# 03_-_Power.net
KiCad netlist of a schematic drawn in Altium Designer
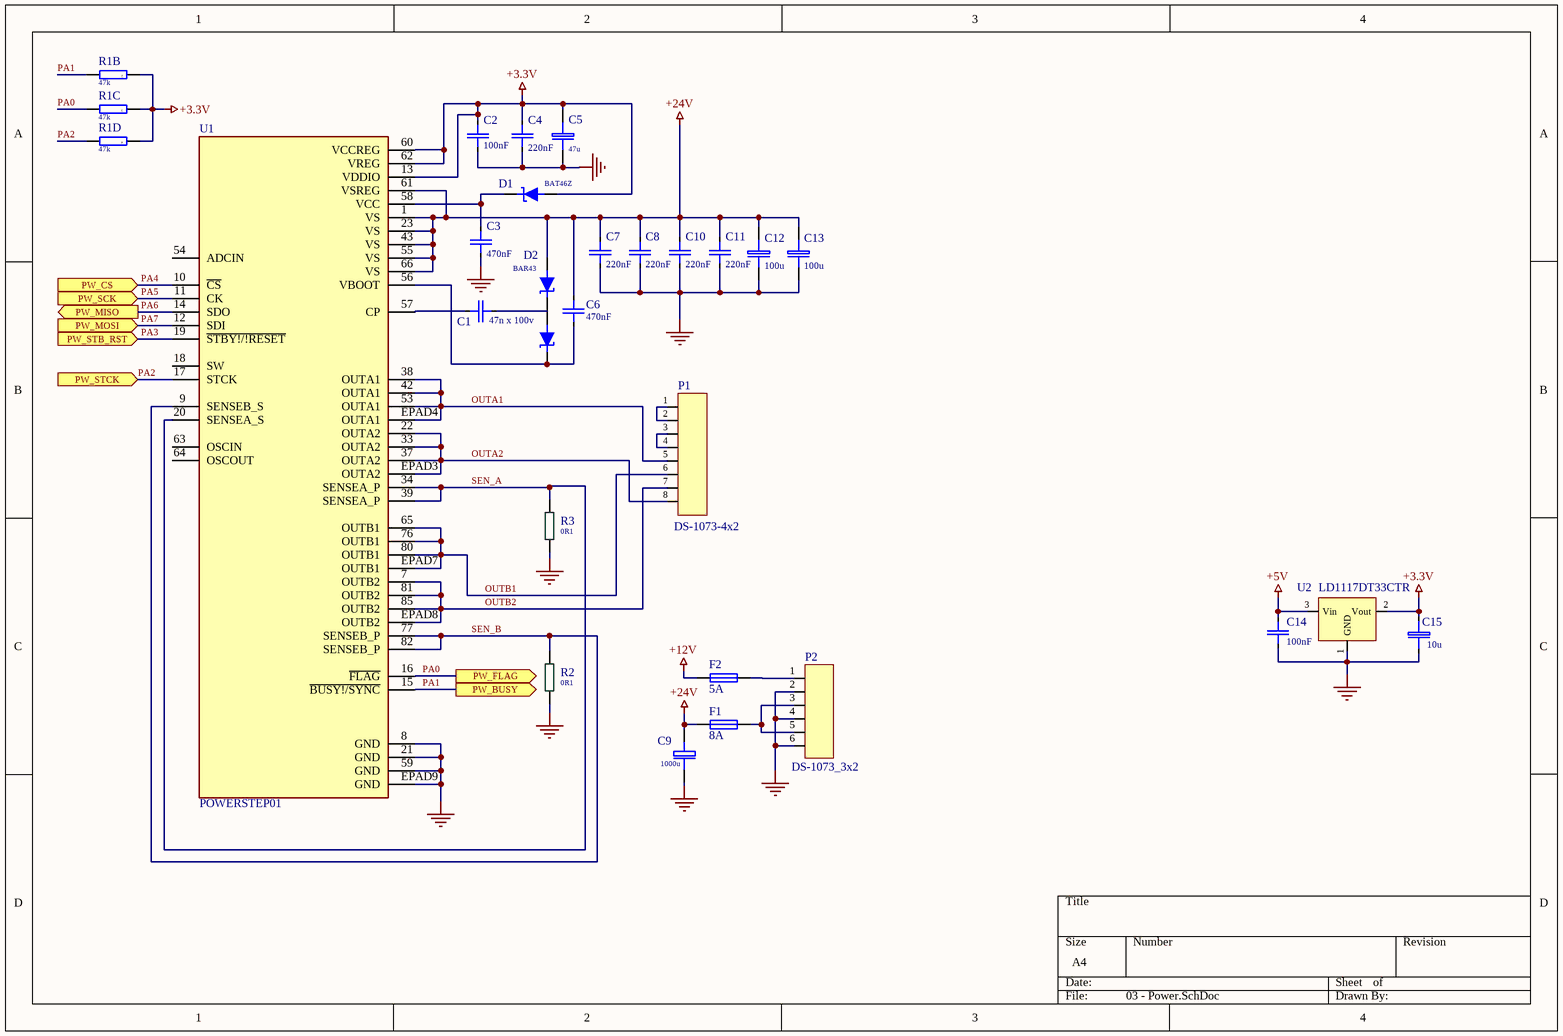
[diagram p0: 03 - Power.SchDoc]

(export (version "E")
  (design (tool "Eeschema 10.0.6"))
  (components
    (comp (ref "C1")
      (value "47n x 100v")
      (footprint "CAP: 0805")
      (description "SMD-0805")
      (libsource (lib "RCL_SMD_Integrated_Library") (part "C-0805"))
    )
    (comp (ref "C2")
      (value "100nF")
      (footprint "CAP: 0805")
      (description "SMD-0805")
      (libsource (lib "RCL_SMD_Integrated_Library") (part "C-0805"))
    )
    (comp (ref "C3")
      (value "470nF")
      (footprint "CAP: 0805")
      (description "SMD-0805")
      (libsource (lib "RCL_SMD_Integrated_Library") (part "C-0805"))
    )
    (comp (ref "C4")
      (value "220nF")
      (footprint "CAP: 0805")
      (description "SMD-0805")
      (libsource (lib "RCL_SMD_Integrated_Library") (part "C-0805"))
    )
    (comp (ref "C5")
      (value "47u")
      (footprint "EL SMD Case C D5x5.3 h5.4(0505)")
      (description "EL 50V SMD Case C D5x5.3 h5.4")
      (libsource (lib "SMD-RCL") (part "EL 10u/50V"))
    )
    (comp (ref "C6")
      (value "470nF")
      (footprint "CAP: 0805")
      (description "SMD-0805")
      (libsource (lib "RCL_SMD_Integrated_Library") (part "C-0805"))
    )
    (comp (ref "C7")
      (value "220nF")
      (footprint "CAP: 0805")
      (description "SMD-0805")
      (libsource (lib "RCL_SMD_Integrated_Library") (part "C-0805"))
    )
    (comp (ref "C8")
      (value "220nF")
      (footprint "CAP: 0805")
      (description "SMD-0805")
      (libsource (lib "RCL_SMD_Integrated_Library") (part "C-0805"))
    )
    (comp (ref "C9")
      (value "1000u")
      (footprint "El-d13-h21-F5.08")
      (description "35V 105C 34m 1.8A 5000h")
      (libsource (lib "Cap-El") (part "1000u-35V 105F"))
    )
    (comp (ref "C10")
      (value "220nF")
      (footprint "CAP: 0805")
      (description "SMD-0805")
      (libsource (lib "RCL_SMD_Integrated_Library") (part "C-0805"))
    )
    (comp (ref "C11")
      (value "220nF")
      (footprint "CAP: 0805")
      (description "SMD-0805")
      (libsource (lib "RCL_SMD_Integrated_Library") (part "C-0805"))
    )
    (comp (ref "C12")
      (value "100u")
      (footprint "EL SMD Case G D10x10.3 h10.2(1010)")
      (description "EL 35V SMD Case G D10x10.3h10.5")
      (libsource (lib "SMD-RCL") (part "EL 100u/35V"))
    )
    (comp (ref "C13")
      (value "100u")
      (footprint "EL SMD Case G D10x10.3 h10.2(1010)")
      (description "EL 35V SMD Case G D10x10.3h10.5")
      (libsource (lib "SMD-RCL") (part "EL 100u/35V"))
    )
    (comp (ref "C14")
      (value "100nF")
      (footprint "CAP: 0805")
      (description "SMD-0805")
      (libsource (lib "RCL_SMD_Integrated_Library") (part "C-0805"))
    )
    (comp (ref "C15")
      (value "10u")
      (footprint "EL Case A (3216-18)")
      (description "El Case A (2012-12)")
      (libsource (lib "RCL_SMD_Integrated_Library") (part "EL 10u/16V Tant."))
    )
    (comp (ref "D1")
      (value "BAT46Z")
      (footprint "SOD123")
      (description "SMD-SOT123 60V 15mA 2.2pF 1nS")
      (libsource (lib "Diodes") (part "1N6263"))
    )
    (comp (ref "D2")
      (value "BAR43")
      (footprint "SOT23")
      (description "SMD-SOT23 30V 0.2A 5nS 10pF")
      (libsource (lib "Diodes") (part "BAT54S"))
    )
    (comp (ref "F1")
      (value "8A")
      (footprint "Littelfuse 0451/453")
      (description "0451003")
      (libsource (lib "stm32_Integrated_Library") (part "Littelfuse 0451"))
    )
    (comp (ref "F2")
      (value "5A")
      (footprint "Littelfuse 0451/453")
      (description "0451003")
      (libsource (lib "stm32_Integrated_Library") (part "Littelfuse 0451"))
    )
    (comp (ref "P1")
      (value "DS-1073-4x2")
      (footprint "DS-1073-4x2")
      (libsource (lib "stm32_Integrated_Library") (part "DS-1073-4x2"))
    )
    (comp (ref "P2")
      (value "DS-1073_3x2")
      (footprint "DS-1073-2x3")
      (libsource (lib "stm32_Integrated_Library") (part "DS-1073_3x2"))
    )
    (comp (ref "R1")
      (value "47k")
      (footprint "RM4x0603")
      (description "SMD 4RM-0603 1\\16W 5%")
      (libsource (lib "SMD-RCL") (part "4RM-0603"))
    )
    (comp (ref "R2")
      (value "0R1")
      (footprint "R2512")
      (description "SMD 2512 1W 5% 200V")
      (libsource (lib "SMD-RCL") (part "R-2512"))
    )
    (comp (ref "R3")
      (value "0R1")
      (footprint "R2512")
      (description "SMD 2512 1W 5% 200V")
      (libsource (lib "SMD-RCL") (part "R-2512"))
    )
    (comp (ref "U1")
      (value "POWERSTEP01")
      (footprint "POWERSTEP01")
      (description "Bipolar Motor Driver Power MOSFET SPI 89-VFQFPN _11x14_")
      (fields (field (name "MF") "STMicroelectronics"))
      (libsource (lib "stm32_Integrated_Library") (part "POWERSTEP01"))
    )
    (comp (ref "U2")
      (value "LD1117DT33CTR")
      (footprint "DPAK")
      (libsource (lib "stm32_Integrated_Library") (part "LD1117DT33CTR"))
    )
  )
  (nets
    (net (code "1") (name "+3.3V") (class "Default")
      (node (ref "C15") (pin "1") (pinfunction "1_1") (pintype "passive"))
      (node (ref "C2") (pin "2") (pinfunction "2_2") (pintype "passive"))
      (node (ref "C4") (pin "1") (pinfunction "1_1") (pintype "passive"))
      (node (ref "C5") (pin "1") (pinfunction "+_1") (pintype "passive"))
      (node (ref "D1") (pin "1") (pinfunction "A_1") (pintype "passive"))
      (node (ref "R1") (pin "2") (pinfunction "2_2") (pintype "passive"))
      (node (ref "R1") (pin "3") (pinfunction "3_3") (pintype "passive"))
      (node (ref "R1") (pin "4") (pinfunction "4_4") (pintype "passive"))
      (node (ref "U1") (pin "13") (pinfunction "VDDIO_13") (pintype "power_in"))
      (node (ref "U1") (pin "60") (pinfunction "VCCREG_60") (pintype "power_in"))
      (node (ref "U1") (pin "62") (pinfunction "VREG_62") (pintype "power_in"))
      (node (ref "U2") (pin "2") (pinfunction "Vout_2") (pintype "passive"))
    )
    (net (code "2") (name "+5V") (class "Default")
      (node (ref "C14") (pin "2") (pinfunction "2_2") (pintype "passive"))
      (node (ref "U2") (pin "3") (pinfunction "Vin_3") (pintype "passive"))
    )
    (net (code "3") (name "+12V") (class "Default")
      (node (ref "F2") (pin "1") (pinfunction "1_1") (pintype "passive"))
    )
    (net (code "4") (name "+24V") (class "Default")
      (node (ref "C10") (pin "1") (pinfunction "1_1") (pintype "passive"))
      (node (ref "C11") (pin "1") (pinfunction "1_1") (pintype "passive"))
      (node (ref "C12") (pin "1") (pinfunction "1_1") (pintype "passive"))
      (node (ref "C13") (pin "1") (pinfunction "1_1") (pintype "passive"))
      (node (ref "C6") (pin "1") (pinfunction "1_1") (pintype "passive"))
      (node (ref "C7") (pin "1") (pinfunction "1_1") (pintype "passive"))
      (node (ref "C8") (pin "1") (pinfunction "1_1") (pintype "passive"))
      (node (ref "C9") (pin "1") (pinfunction "1_1") (pintype "passive"))
      (node (ref "D2") (pin "1") (pinfunction "1_1") (pintype "passive"))
      (node (ref "F1") (pin "1") (pinfunction "1_1") (pintype "passive"))
      (node (ref "U1") (pin "1") (pinfunction "VS_1") (pintype "passive"))
      (node (ref "U1") (pin "23") (pinfunction "VS_23") (pintype "passive"))
      (node (ref "U1") (pin "43") (pinfunction "VS_43") (pintype "passive"))
      (node (ref "U1") (pin "55") (pinfunction "VS_55") (pintype "passive"))
      (node (ref "U1") (pin "61") (pinfunction "VSREG_61") (pintype "passive"))
      (node (ref "U1") (pin "66") (pinfunction "VS_66") (pintype "passive"))
    )
    (net (code "5") (name "/OUTA1") (class "Default")
      (node (ref "P1") (pin "5") (pintype "passive"))
      (node (ref "U1") (pin "38") (pinfunction "OUTA1_38") (pintype "power_in"))
      (node (ref "U1") (pin "42") (pinfunction "OUTA1_42") (pintype "power_in"))
      (node (ref "U1") (pin "53") (pinfunction "OUTA1_53") (pintype "power_in"))
      (node (ref "U1") (pin "EPAD4") (pinfunction "OUTA1_EPAD4") (pintype "power_in"))
    )
    (net (code "6") (name "/OUTA2") (class "Default")
      (node (ref "P1") (pin "8") (pintype "passive"))
      (node (ref "U1") (pin "22") (pinfunction "OUTA2_22") (pintype "power_in"))
      (node (ref "U1") (pin "33") (pinfunction "OUTA2_33") (pintype "power_in"))
      (node (ref "U1") (pin "37") (pinfunction "OUTA2_37") (pintype "power_in"))
      (node (ref "U1") (pin "EPAD3") (pinfunction "OUTA2_EPAD3") (pintype "power_in"))
    )
    (net (code "7") (name "/OUTB1") (class "Default")
      (node (ref "P1") (pin "6") (pintype "passive"))
      (node (ref "U1") (pin "65") (pinfunction "OUTB1_65") (pintype "power_in"))
      (node (ref "U1") (pin "76") (pinfunction "OUTB1_76") (pintype "power_in"))
      (node (ref "U1") (pin "80") (pinfunction "OUTB1_80") (pintype "power_in"))
      (node (ref "U1") (pin "EPAD7") (pinfunction "OUTB1_EPAD7") (pintype "power_in"))
    )
    (net (code "8") (name "/OUTB2") (class "Default")
      (node (ref "P1") (pin "7") (pintype "passive"))
      (node (ref "U1") (pin "7") (pinfunction "OUTB2_7") (pintype "power_in"))
      (node (ref "U1") (pin "81") (pinfunction "OUTB2_81") (pintype "power_in"))
      (node (ref "U1") (pin "85") (pinfunction "OUTB2_85") (pintype "power_in"))
      (node (ref "U1") (pin "EPAD8") (pinfunction "OUTB2_EPAD8") (pintype "power_in"))
    )
    (net (code "9") (name "/PA0") (class "Default")
      (node (ref "R1") (pin "6") (pinfunction "6_6") (pintype "passive"))
      (node (ref "U1") (pin "16") (pinfunction "~{FLAG}_16") (pintype "passive"))
    )
    (net (code "10") (name "/PA1") (class "Default")
      (node (ref "R1") (pin "7") (pinfunction "7_7") (pintype "passive"))
      (node (ref "U1") (pin "15") (pinfunction "~{BUSY!/SYNC}_15") (pintype "passive"))
    )
    (net (code "11") (name "/PA2") (class "Default")
      (node (ref "R1") (pin "5") (pinfunction "5_5") (pintype "passive"))
      (node (ref "U1") (pin "17") (pinfunction "STCK_17") (pintype "passive"))
    )
    (net (code "12") (name "/PA3") (class "Default")
      (node (ref "U1") (pin "19") (pinfunction "~{STBY!/!RESET}_19") (pintype "passive"))
    )
    (net (code "13") (name "/PA4") (class "Default")
      (node (ref "U1") (pin "10") (pinfunction "~{CS}_10") (pintype "passive"))
    )
    (net (code "14") (name "/PA5") (class "Default")
      (node (ref "U1") (pin "11") (pinfunction "CK_11") (pintype "passive"))
    )
    (net (code "15") (name "/PA6") (class "Default")
      (node (ref "U1") (pin "14") (pinfunction "SDO_14") (pintype "passive"))
    )
    (net (code "16") (name "/PA7") (class "Default")
      (node (ref "U1") (pin "12") (pinfunction "SDI_12") (pintype "passive"))
    )
    (net (code "17") (name "/SEN_A") (class "Default")
      (node (ref "R3") (pin "2") (pinfunction "2_2") (pintype "passive"))
      (node (ref "U1") (pin "20") (pinfunction "SENSEA_S_20") (pintype "passive"))
      (node (ref "U1") (pin "34") (pinfunction "SENSEA_P_34") (pintype "passive"))
      (node (ref "U1") (pin "39") (pinfunction "SENSEA_P_39") (pintype "passive"))
    )
    (net (code "18") (name "/SEN_B") (class "Default")
      (node (ref "R2") (pin "2") (pinfunction "2_2") (pintype "passive"))
      (node (ref "U1") (pin "77") (pinfunction "SENSEB_P_77") (pintype "passive"))
      (node (ref "U1") (pin "82") (pinfunction "SENSEB_P_82") (pintype "passive"))
      (node (ref "U1") (pin "9") (pinfunction "SENSEB_S_9") (pintype "passive"))
    )
    (net (code "19") (name "GND") (class "Default")
      (node (ref "C10") (pin "2") (pinfunction "2_2") (pintype "passive"))
      (node (ref "C11") (pin "2") (pinfunction "2_2") (pintype "passive"))
      (node (ref "C12") (pin "2") (pinfunction "2_2") (pintype "passive"))
      (node (ref "C13") (pin "2") (pinfunction "2_2") (pintype "passive"))
      (node (ref "C14") (pin "1") (pinfunction "1_1") (pintype "passive"))
      (node (ref "C15") (pin "2") (pinfunction "2_2") (pintype "passive"))
      (node (ref "C2") (pin "1") (pinfunction "1_1") (pintype "passive"))
      (node (ref "C3") (pin "2") (pinfunction "2_2") (pintype "passive"))
      (node (ref "C4") (pin "2") (pinfunction "2_2") (pintype "passive"))
      (node (ref "C5") (pin "2") (pinfunction "-_2") (pintype "passive"))
      (node (ref "C7") (pin "2") (pinfunction "2_2") (pintype "passive"))
      (node (ref "C8") (pin "2") (pinfunction "2_2") (pintype "passive"))
      (node (ref "C9") (pin "2") (pinfunction "2_2") (pintype "passive"))
      (node (ref "P2") (pin "2") (pintype "passive"))
      (node (ref "P2") (pin "4") (pintype "passive"))
      (node (ref "P2") (pin "6") (pintype "passive"))
      (node (ref "R2") (pin "1") (pinfunction "1_1") (pintype "passive"))
      (node (ref "R3") (pin "1") (pinfunction "1_1") (pintype "passive"))
      (node (ref "U1") (pin "21") (pinfunction "GND_21") (pintype "power_in"))
      (node (ref "U1") (pin "59") (pinfunction "GND_59") (pintype "power_in"))
      (node (ref "U1") (pin "8") (pinfunction "GND_8") (pintype "power_in"))
      (node (ref "U1") (pin "EPAD9") (pinfunction "GND_EPAD9") (pintype "power_in"))
      (node (ref "U2") (pin "1") (pinfunction "GND_1") (pintype "passive"))
    )
    (net (code "20") (name "Net-(C1-Pad2)") (class "Default")
      (node (ref "C1") (pin "2") (pinfunction "2_2") (pintype "passive"))
      (node (ref "D2") (pin "3") (pinfunction "3_3") (pintype "passive"))
    )
    (net (code "21") (name "Net-(D1-C)") (class "Default")
      (node (ref "C3") (pin "1") (pinfunction "1_1") (pintype "passive"))
      (node (ref "D1") (pin "2") (pinfunction "C_2") (pintype "passive"))
      (node (ref "U1") (pin "58") (pinfunction "VCC_58") (pintype "power_in"))
    )
    (net (code "22") (name "Net-(F1-Pad2)") (class "Default")
      (node (ref "F1") (pin "2") (pinfunction "2_2") (pintype "passive"))
      (node (ref "P2") (pin "3") (pintype "passive"))
      (node (ref "P2") (pin "5") (pintype "passive"))
    )
    (net (code "23") (name "Net-(F2-Pad2)") (class "Default")
      (node (ref "F2") (pin "2") (pinfunction "2_2") (pintype "passive"))
      (node (ref "P2") (pin "1") (pintype "passive"))
    )
    (net (code "24") (name "Net-(P1-Pad1)") (class "Default")
      (node (ref "P1") (pin "1") (pintype "passive"))
      (node (ref "P1") (pin "2") (pintype "passive"))
    )
    (net (code "25") (name "Net-(P1-Pad3)") (class "Default")
      (node (ref "P1") (pin "3") (pintype "passive"))
      (node (ref "P1") (pin "4") (pintype "passive"))
    )
    (net (code "26") (name "Net-(U1-CP)") (class "Default")
      (node (ref "C1") (pin "1") (pinfunction "1_1") (pintype "passive"))
      (node (ref "U1") (pin "57") (pinfunction "CP_57") (pintype "passive"))
    )
    (net (code "27") (name "Net-(U1-VBOOT)") (class "Default")
      (node (ref "C6") (pin "2") (pinfunction "2_2") (pintype "passive"))
      (node (ref "D2") (pin "2") (pinfunction "2_2") (pintype "passive"))
      (node (ref "U1") (pin "56") (pinfunction "VBOOT_56") (pintype "power_in"))
    )
    (net (code "28") (name "unconnected-(U1-ADCIN-Pad54)") (class "Default")
      (node (ref "U1") (pin "54") (pinfunction "ADCIN_54") (pintype "passive"))
    )
    (net (code "29") (name "unconnected-(U1-OSCIN-Pad63)") (class "Default")
      (node (ref "U1") (pin "63") (pinfunction "OSCIN_63") (pintype "passive"))
    )
    (net (code "30") (name "unconnected-(U1-OSCOUT-Pad64)") (class "Default")
      (node (ref "U1") (pin "64") (pinfunction "OSCOUT_64") (pintype "passive"))
    )
    (net (code "31") (name "unconnected-(U1-SW-Pad18)") (class "Default")
      (node (ref "U1") (pin "18") (pinfunction "SW_18") (pintype "passive"))
    )
  )
)
